# EL2.net
KiCad netlist of a schematic drawn in EAGLE
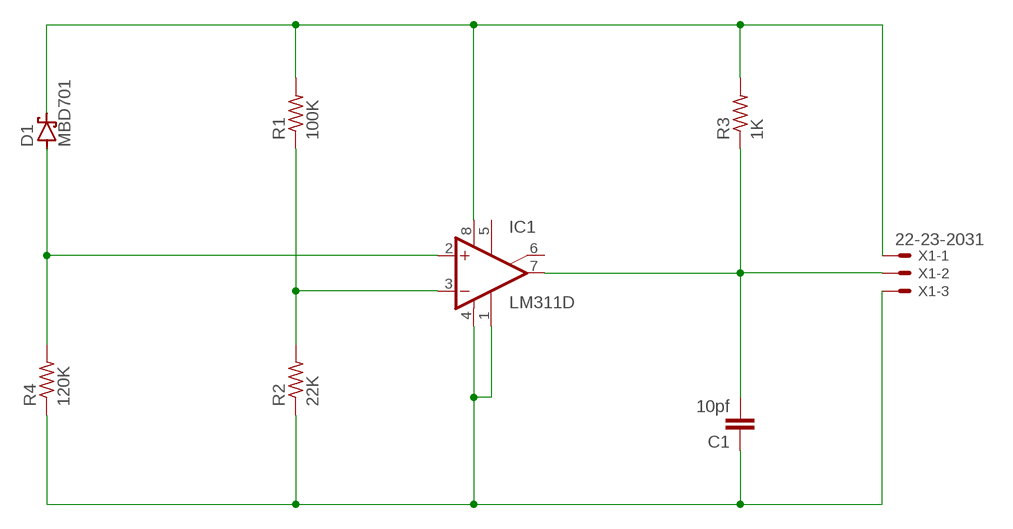
[diagram p0: schematic, sheet 1]

(export (version "E")
  (design (tool "Eeschema 10.0.6"))
  (components
    (comp (ref "C1")
      (value "10pf")
      (footprint "eagle-import:C0603")
      (libsource (lib "eagle-import") (part "C-EUC0603"))
    )
    (comp (ref "D1")
      (value "MBD701")
      (footprint "eagle-import:TO92H")
      (libsource (lib "eagle-import") (part "MBD701"))
    )
    (comp (ref "IC1")
      (value "LM311D")
      (footprint "eagle-import:SO08")
      (libsource (lib "eagle-import") (part "LM311D"))
    )
    (comp (ref "R1")
      (value "100K")
      (footprint "eagle-import:R0603")
      (libsource (lib "eagle-import") (part "R-US_R0603"))
    )
    (comp (ref "R2")
      (value "22K")
      (footprint "eagle-import:R0603")
      (libsource (lib "eagle-import") (part "R-US_R0603"))
    )
    (comp (ref "R3")
      (value "1K")
      (footprint "eagle-import:R0603")
      (libsource (lib "eagle-import") (part "R-US_R0603"))
    )
    (comp (ref "R4")
      (value "120K")
      (footprint "eagle-import:R0603")
      (libsource (lib "eagle-import") (part "R-US_R0603"))
    )
    (comp (ref "X1")
      (value "22-23-2031")
      (footprint "eagle-import:22-23-2031")
      (fields (field (name "MF") "MOLEX"))
      (libsource (lib "eagle-import") (part "22-23-2031"))
    )
  )
  (nets
    (net (code "1") (name "Net-(D1-A)") (class "Default")
      (node (ref "D1") (pin "1") (pinfunction "A_1") (pintype "passive"))
      (node (ref "IC1") (pin "2") (pinfunction "+IN_2") (pintype "input"))
      (node (ref "R4") (pin "2") (pinfunction "2_2") (pintype "passive"))
    )
    (net (code "2") (name "Net-(D1-C)") (class "Default")
      (node (ref "D1") (pin "2") (pinfunction "C_2") (pintype "passive"))
      (node (ref "IC1") (pin "8") (pinfunction "V+_8") (pintype "power_in"))
      (node (ref "R1") (pin "2") (pinfunction "2_2") (pintype "passive"))
      (node (ref "R3") (pin "2") (pinfunction "2_2") (pintype "passive"))
      (node (ref "X1") (pin "1") (pinfunction "S_1") (pintype "passive"))
    )
    (net (code "3") (name "Net-(IC1--IN)") (class "Default")
      (node (ref "IC1") (pin "3") (pinfunction "-IN_3") (pintype "input"))
      (node (ref "R1") (pin "1") (pinfunction "1_1") (pintype "passive"))
      (node (ref "R2") (pin "2") (pinfunction "2_2") (pintype "passive"))
    )
    (net (code "4") (name "Net-(IC1-GND)") (class "Default")
      (node (ref "C1") (pin "1") (pinfunction "1_1") (pintype "passive"))
      (node (ref "IC1") (pin "1") (pinfunction "GND_1") (pintype "passive"))
      (node (ref "IC1") (pin "4") (pinfunction "V-_4") (pintype "power_in"))
      (node (ref "R2") (pin "1") (pinfunction "1_1") (pintype "passive"))
      (node (ref "R4") (pin "1") (pinfunction "1_1") (pintype "passive"))
      (node (ref "X1") (pin "3") (pinfunction "S_3") (pintype "passive"))
    )
    (net (code "5") (name "Net-(IC1-OUT)") (class "Default")
      (node (ref "C1") (pin "2") (pinfunction "2_2") (pintype "passive"))
      (node (ref "IC1") (pin "7") (pinfunction "OUT_7") (pintype "output"))
      (node (ref "R3") (pin "1") (pinfunction "1_1") (pintype "passive"))
      (node (ref "X1") (pin "2") (pinfunction "S_2") (pintype "passive"))
    )
    (net (code "6") (name "unconnected-(IC1-ON-Pad5)") (class "Default")
      (node (ref "IC1") (pin "5") (pinfunction "ON_5") (pintype "passive"))
    )
    (net (code "7") (name "unconnected-(IC1-ON{slash}STR-Pad6)") (class "Default")
      (node (ref "IC1") (pin "6") (pinfunction "ON/STR_6") (pintype "passive"))
    )
  )
)
